# POWER.net
KiCad netlist of a schematic drawn in Altium Designer
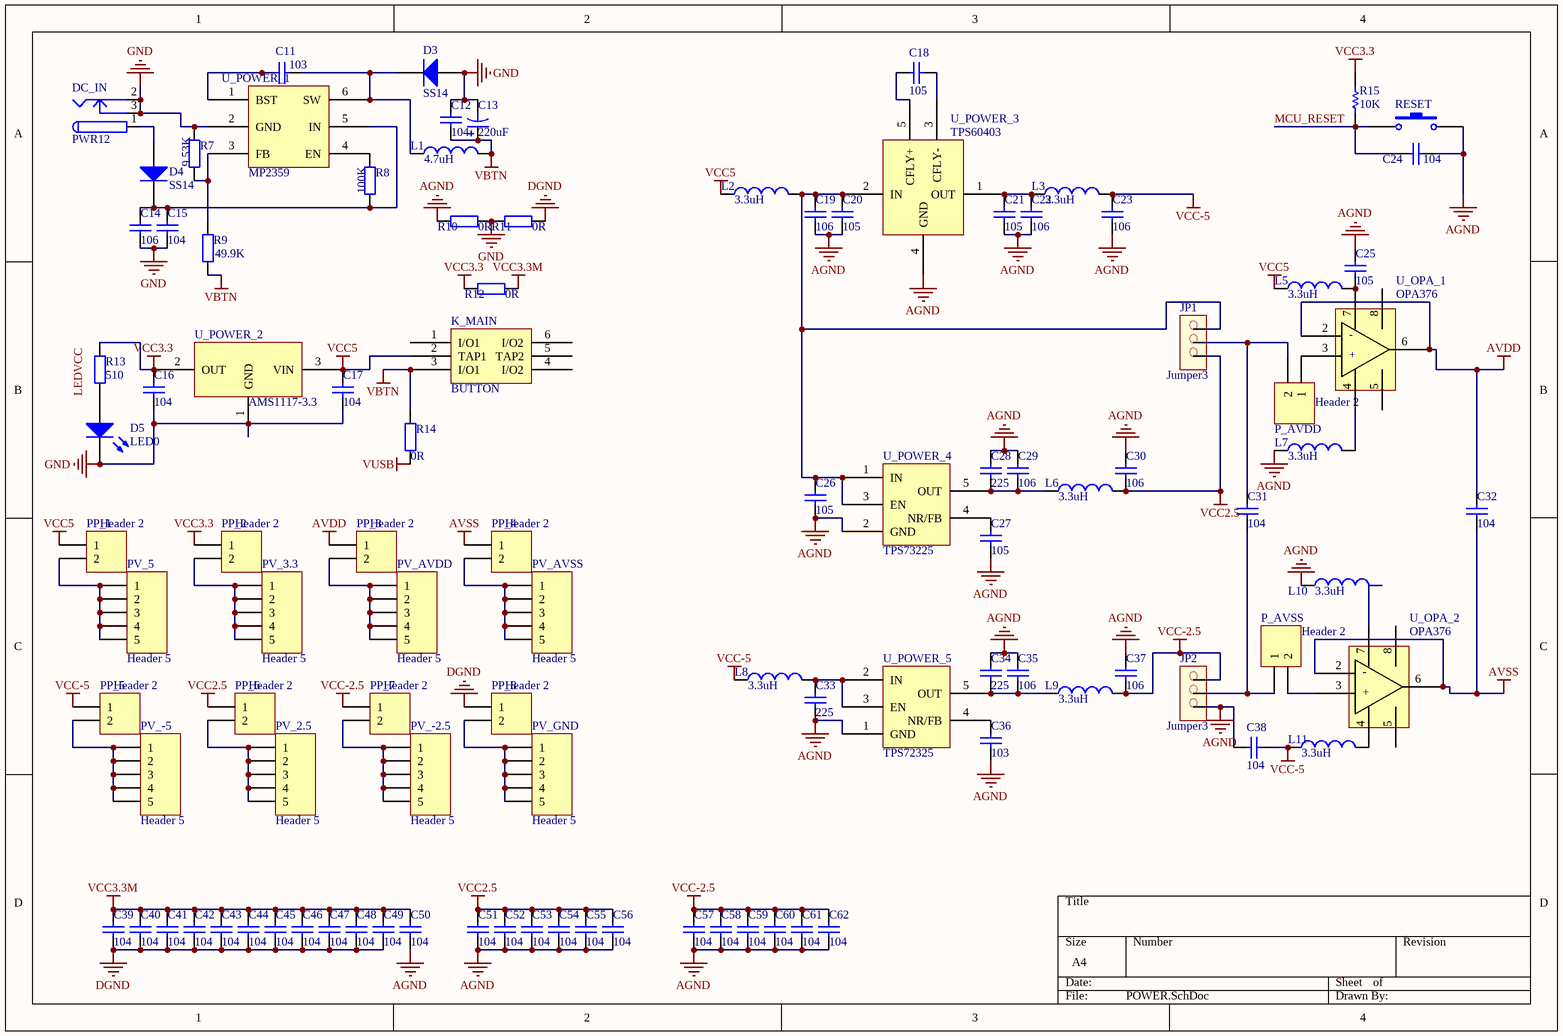
[diagram p0: POWER.SchDoc]

(export (version "E")
  (design (tool "Eeschema 10.0.6"))
  (components
    (comp (ref "C11")
      (value "103")
      (footprint "SMT-0603")
      (description "Capacitor")
      (fields (field (name "Comment") "Cap") (field (name "PUBLISHER") "Altium Limited"))
      (libsource (lib "Miscellaneous Devices") (part "Cap"))
    )
    (comp (ref "C12")
      (value "104")
      (footprint "SMT-0603")
      (description "Capacitor")
      (fields (field (name "Comment") "Cap") (field (name "PUBLISHER") "Altium Limited"))
      (libsource (lib "Miscellaneous Devices") (part "Cap"))
    )
    (comp (ref "C13")
      (value "220uF")
      (footprint "SMT-Cap100~220uF(5x5.4)_10V")
      (description "Polarized Capacitor (Radial)")
      (fields (field (name "Comment") "Cap Pol1") (field (name "PUBLISHER") "Altium Limited"))
      (libsource (lib "Miscellaneous Devices") (part "Cap Pol1"))
    )
    (comp (ref "C14")
      (value "106")
      (footprint "SMT-0603")
      (description "Capacitor")
      (fields (field (name "Comment") "Cap") (field (name "PUBLISHER") "Altium Limited"))
      (libsource (lib "Miscellaneous Devices") (part "Cap"))
    )
    (comp (ref "C15")
      (value "104")
      (footprint "SMT-0603")
      (description "Capacitor")
      (fields (field (name "Comment") "Cap") (field (name "PUBLISHER") "Altium Limited"))
      (libsource (lib "Miscellaneous Devices") (part "Cap"))
    )
    (comp (ref "C16")
      (value "104")
      (footprint "SMT-0603")
      (description "Capacitor")
      (fields (field (name "Comment") "Cap") (field (name "PUBLISHER") "Altium Limited"))
      (libsource (lib "Miscellaneous Devices") (part "Cap"))
    )
    (comp (ref "C17")
      (value "104")
      (footprint "SMT-0603")
      (description "Capacitor")
      (fields (field (name "Comment") "Cap") (field (name "PUBLISHER") "Altium Limited"))
      (libsource (lib "Miscellaneous Devices") (part "Cap"))
    )
    (comp (ref "C18")
      (value "105")
      (footprint "SMT-0603")
      (description "Capacitor")
      (fields (field (name "Comment") "Cap") (field (name "PUBLISHER") "Altium Limited"))
      (libsource (lib "Miscellaneous Devices") (part "Cap"))
    )
    (comp (ref "C19")
      (value "106")
      (footprint "SMT-0603")
      (description "Capacitor")
      (fields (field (name "Comment") "Cap") (field (name "PUBLISHER") "Altium Limited"))
      (libsource (lib "Miscellaneous Devices") (part "Cap"))
    )
    (comp (ref "C20")
      (value "105")
      (footprint "SMT-0603")
      (description "Capacitor")
      (fields (field (name "Comment") "Cap") (field (name "PUBLISHER") "Altium Limited"))
      (libsource (lib "Miscellaneous Devices") (part "Cap"))
    )
    (comp (ref "C21")
      (value "105")
      (footprint "SMT-0603")
      (description "Capacitor")
      (fields (field (name "Comment") "Cap") (field (name "PUBLISHER") "Altium Limited"))
      (libsource (lib "Miscellaneous Devices") (part "Cap"))
    )
    (comp (ref "C22")
      (value "106")
      (footprint "SMT-0603")
      (description "Capacitor")
      (fields (field (name "Comment") "Cap") (field (name "PUBLISHER") "Altium Limited"))
      (libsource (lib "Miscellaneous Devices") (part "Cap"))
    )
    (comp (ref "C23")
      (value "106")
      (footprint "SMT-0603")
      (description "Capacitor")
      (fields (field (name "Comment") "Cap") (field (name "PUBLISHER") "Altium Limited"))
      (libsource (lib "Miscellaneous Devices") (part "Cap"))
    )
    (comp (ref "C24")
      (value "104")
      (footprint "SMT-0603")
      (description "Capacitor")
      (fields (field (name "Comment") "Cap") (field (name "PUBLISHER") "Altium Limited"))
      (libsource (lib "Miscellaneous Devices") (part "Cap"))
    )
    (comp (ref "C25")
      (value "105")
      (footprint "SMT-0603")
      (description "Capacitor")
      (fields (field (name "Comment") "Cap") (field (name "PUBLISHER") "Altium Limited"))
      (libsource (lib "Miscellaneous Devices") (part "Cap"))
    )
    (comp (ref "C26")
      (value "105")
      (footprint "SMT-0603")
      (description "Capacitor")
      (fields (field (name "Comment") "Cap") (field (name "PUBLISHER") "Altium Limited"))
      (libsource (lib "Miscellaneous Devices") (part "Cap"))
    )
    (comp (ref "C27")
      (value "105")
      (footprint "SMT-0603")
      (description "Capacitor")
      (fields (field (name "Comment") "Cap") (field (name "PUBLISHER") "Altium Limited"))
      (libsource (lib "Miscellaneous Devices") (part "Cap"))
    )
    (comp (ref "C28")
      (value "225")
      (footprint "SMT-0603")
      (description "Capacitor")
      (fields (field (name "Comment") "Cap") (field (name "PUBLISHER") "Altium Limited"))
      (libsource (lib "Miscellaneous Devices") (part "Cap"))
    )
    (comp (ref "C29")
      (value "106")
      (footprint "SMT-0603")
      (description "Capacitor")
      (fields (field (name "Comment") "Cap") (field (name "PUBLISHER") "Altium Limited"))
      (libsource (lib "Miscellaneous Devices") (part "Cap"))
    )
    (comp (ref "C30")
      (value "106")
      (footprint "SMT-0603")
      (description "Capacitor")
      (fields (field (name "Comment") "Cap") (field (name "PUBLISHER") "Altium Limited"))
      (libsource (lib "Miscellaneous Devices") (part "Cap"))
    )
    (comp (ref "C31")
      (value "104")
      (footprint "SMT-0603")
      (description "Capacitor")
      (fields (field (name "Comment") "Cap") (field (name "PUBLISHER") "Altium Limited"))
      (libsource (lib "Miscellaneous Devices") (part "Cap"))
    )
    (comp (ref "C32")
      (value "104")
      (footprint "SMT-0603")
      (description "Capacitor")
      (fields (field (name "Comment") "Cap") (field (name "PUBLISHER") "Altium Limited"))
      (libsource (lib "Miscellaneous Devices") (part "Cap"))
    )
    (comp (ref "C33")
      (value "225")
      (footprint "SMT-0603")
      (description "Capacitor")
      (fields (field (name "Comment") "Cap") (field (name "PUBLISHER") "Altium Limited"))
      (libsource (lib "Miscellaneous Devices") (part "Cap"))
    )
    (comp (ref "C34")
      (value "225")
      (footprint "SMT-0603")
      (description "Capacitor")
      (fields (field (name "Comment") "Cap") (field (name "PUBLISHER") "Altium Limited"))
      (libsource (lib "Miscellaneous Devices") (part "Cap"))
    )
    (comp (ref "C35")
      (value "106")
      (footprint "SMT-0603")
      (description "Capacitor")
      (fields (field (name "Comment") "Cap") (field (name "PUBLISHER") "Altium Limited"))
      (libsource (lib "Miscellaneous Devices") (part "Cap"))
    )
    (comp (ref "C36")
      (value "103")
      (footprint "SMT-0603")
      (description "Capacitor")
      (fields (field (name "Comment") "Cap") (field (name "PUBLISHER") "Altium Limited"))
      (libsource (lib "Miscellaneous Devices") (part "Cap"))
    )
    (comp (ref "C37")
      (value "106")
      (footprint "SMT-0603")
      (description "Capacitor")
      (fields (field (name "Comment") "Cap") (field (name "PUBLISHER") "Altium Limited"))
      (libsource (lib "Miscellaneous Devices") (part "Cap"))
    )
    (comp (ref "C38")
      (value "104")
      (footprint "SMT-0603")
      (description "Capacitor")
      (fields (field (name "Comment") "Cap") (field (name "PUBLISHER") "Altium Limited"))
      (libsource (lib "Miscellaneous Devices") (part "Cap"))
    )
    (comp (ref "C39")
      (value "104")
      (footprint "SMT-0603")
      (description "Capacitor")
      (fields (field (name "Comment") "Cap") (field (name "PUBLISHER") "Altium Limited"))
      (libsource (lib "Miscellaneous Devices") (part "Cap"))
    )
    (comp (ref "C40")
      (value "104")
      (footprint "SMT-0603")
      (description "Capacitor")
      (fields (field (name "Comment") "Cap") (field (name "PUBLISHER") "Altium Limited"))
      (libsource (lib "Miscellaneous Devices") (part "Cap"))
    )
    (comp (ref "C41")
      (value "104")
      (footprint "SMT-0603")
      (description "Capacitor")
      (fields (field (name "Comment") "Cap") (field (name "PUBLISHER") "Altium Limited"))
      (libsource (lib "Miscellaneous Devices") (part "Cap"))
    )
    (comp (ref "C42")
      (value "104")
      (footprint "SMT-0603")
      (description "Capacitor")
      (fields (field (name "Comment") "Cap") (field (name "PUBLISHER") "Altium Limited"))
      (libsource (lib "Miscellaneous Devices") (part "Cap"))
    )
    (comp (ref "C43")
      (value "104")
      (footprint "SMT-0603")
      (description "Capacitor")
      (fields (field (name "Comment") "Cap") (field (name "PUBLISHER") "Altium Limited"))
      (libsource (lib "Miscellaneous Devices") (part "Cap"))
    )
    (comp (ref "C44")
      (value "104")
      (footprint "SMT-0603")
      (description "Capacitor")
      (fields (field (name "Comment") "Cap") (field (name "PUBLISHER") "Altium Limited"))
      (libsource (lib "Miscellaneous Devices") (part "Cap"))
    )
    (comp (ref "C45")
      (value "104")
      (footprint "SMT-0603")
      (description "Capacitor")
      (fields (field (name "Comment") "Cap") (field (name "PUBLISHER") "Altium Limited"))
      (libsource (lib "Miscellaneous Devices") (part "Cap"))
    )
    (comp (ref "C46")
      (value "104")
      (footprint "SMT-0603")
      (description "Capacitor")
      (fields (field (name "Comment") "Cap") (field (name "PUBLISHER") "Altium Limited"))
      (libsource (lib "Miscellaneous Devices") (part "Cap"))
    )
    (comp (ref "C47")
      (value "104")
      (footprint "SMT-0603")
      (description "Capacitor")
      (fields (field (name "Comment") "Cap") (field (name "PUBLISHER") "Altium Limited"))
      (libsource (lib "Miscellaneous Devices") (part "Cap"))
    )
    (comp (ref "C48")
      (value "104")
      (footprint "SMT-0603")
      (description "Capacitor")
      (fields (field (name "Comment") "Cap") (field (name "PUBLISHER") "Altium Limited"))
      (libsource (lib "Miscellaneous Devices") (part "Cap"))
    )
    (comp (ref "C49")
      (value "104")
      (footprint "SMT-0603")
      (description "Capacitor")
      (fields (field (name "Comment") "Cap") (field (name "PUBLISHER") "Altium Limited"))
      (libsource (lib "Miscellaneous Devices") (part "Cap"))
    )
    (comp (ref "C50")
      (value "104")
      (footprint "SMT-0603")
      (description "Capacitor")
      (fields (field (name "Comment") "Cap") (field (name "PUBLISHER") "Altium Limited"))
      (libsource (lib "Miscellaneous Devices") (part "Cap"))
    )
    (comp (ref "C51")
      (value "104")
      (footprint "SMT-0603")
      (description "Capacitor")
      (fields (field (name "Comment") "Cap") (field (name "PUBLISHER") "Altium Limited"))
      (libsource (lib "Miscellaneous Devices") (part "Cap"))
    )
    (comp (ref "C52")
      (value "104")
      (footprint "SMT-0603")
      (description "Capacitor")
      (fields (field (name "Comment") "Cap") (field (name "PUBLISHER") "Altium Limited"))
      (libsource (lib "Miscellaneous Devices") (part "Cap"))
    )
    (comp (ref "C53")
      (value "104")
      (footprint "SMT-0603")
      (description "Capacitor")
      (fields (field (name "Comment") "Cap") (field (name "PUBLISHER") "Altium Limited"))
      (libsource (lib "Miscellaneous Devices") (part "Cap"))
    )
    (comp (ref "C54")
      (value "104")
      (footprint "SMT-0603")
      (description "Capacitor")
      (fields (field (name "Comment") "Cap") (field (name "PUBLISHER") "Altium Limited"))
      (libsource (lib "Miscellaneous Devices") (part "Cap"))
    )
    (comp (ref "C55")
      (value "104")
      (footprint "SMT-0603")
      (description "Capacitor")
      (fields (field (name "Comment") "Cap") (field (name "PUBLISHER") "Altium Limited"))
      (libsource (lib "Miscellaneous Devices") (part "Cap"))
    )
    (comp (ref "C56")
      (value "104")
      (footprint "SMT-0603")
      (description "Capacitor")
      (fields (field (name "Comment") "Cap") (field (name "PUBLISHER") "Altium Limited"))
      (libsource (lib "Miscellaneous Devices") (part "Cap"))
    )
    (comp (ref "C57")
      (value "104")
      (footprint "SMT-0603")
      (description "Capacitor")
      (fields (field (name "Comment") "Cap") (field (name "PUBLISHER") "Altium Limited"))
      (libsource (lib "Miscellaneous Devices") (part "Cap"))
    )
    (comp (ref "C58")
      (value "104")
      (footprint "SMT-0603")
      (description "Capacitor")
      (fields (field (name "Comment") "Cap") (field (name "PUBLISHER") "Altium Limited"))
      (libsource (lib "Miscellaneous Devices") (part "Cap"))
    )
    (comp (ref "C59")
      (value "104")
      (footprint "SMT-0603")
      (description "Capacitor")
      (fields (field (name "Comment") "Cap") (field (name "PUBLISHER") "Altium Limited"))
      (libsource (lib "Miscellaneous Devices") (part "Cap"))
    )
    (comp (ref "C60")
      (value "104")
      (footprint "SMT-0603")
      (description "Capacitor")
      (fields (field (name "Comment") "Cap") (field (name "PUBLISHER") "Altium Limited"))
      (libsource (lib "Miscellaneous Devices") (part "Cap"))
    )
    (comp (ref "C61")
      (value "104")
      (footprint "SMT-0603")
      (description "Capacitor")
      (fields (field (name "Comment") "Cap") (field (name "PUBLISHER") "Altium Limited"))
      (libsource (lib "Miscellaneous Devices") (part "Cap"))
    )
    (comp (ref "C62")
      (value "104")
      (footprint "SMT-0603")
      (description "Capacitor")
      (fields (field (name "Comment") "Cap") (field (name "PUBLISHER") "Altium Limited"))
      (libsource (lib "Miscellaneous Devices") (part "Cap"))
    )
    (comp (ref "D3")
      (value "SS14")
      (footprint "SMA")
      (description "3 Amp General Purpose Rectifier")
      (fields (field (name "PUBLISHER") "Altium Limited"))
      (libsource (lib "Miscellaneous Devices") (part "Diode 1N5400"))
    )
    (comp (ref "D4")
      (value "SS14")
      (footprint "SMA")
      (description "3 Amp General Purpose Rectifier")
      (fields (field (name "PUBLISHER") "Altium Limited"))
      (libsource (lib "Miscellaneous Devices") (part "Diode 1N5400"))
    )
    (comp (ref "D5")
      (value "LED0")
      (footprint "K3528")
      (description "Typical INFRARED GaAs LED")
      (fields (field (name "PUBLISHER") "Altium Limited"))
      (libsource (lib "Miscellaneous Devices") (part "LED0"))
    )
    (comp (ref "DC_IN")
      (value "PWR12")
      (footprint "D-DCJACK")
      (description "Low Voltage Power Supply Connector")
      (fields (field (name "PUBLISHER") "Altium Limited"))
      (libsource (lib "Miscellaneous Connectors") (part "PWR2.5"))
    )
    (comp (ref "JP1") (value "Jumper3") (footprint "HDR1X3") (libsource (lib "*") (part "Jumper3")))
    (comp (ref "JP2") (value "Jumper3") (footprint "HDR1X3") (libsource (lib "*") (part "Jumper3")))
    (comp (ref "K_MAIN")
      (value "BUTTON")
      (footprint "Auto_lock_SW_7X7")
      (libsource (lib "STM_ALL") (part "BUTTON"))
    )
    (comp (ref "L1")
      (value "4.7uH")
      (footprint "SMT-0805")
      (description "Inductor")
      (fields (field (name "PUBLISHER") "Altium Limited"))
      (libsource (lib "Miscellaneous Devices") (part "Inductor"))
    )
    (comp (ref "L2")
      (value "3.3uH")
      (footprint "SMT-0805")
      (description "Inductor")
      (fields (field (name "PUBLISHER") "Altium Limited"))
      (libsource (lib "Miscellaneous Devices") (part "Inductor"))
    )
    (comp (ref "L3")
      (value "3.3uH")
      (footprint "SMT-0805")
      (description "Inductor")
      (fields (field (name "PUBLISHER") "Altium Limited"))
      (libsource (lib "Miscellaneous Devices") (part "Inductor"))
    )
    (comp (ref "L5")
      (value "3.3uH")
      (footprint "SMT-0805")
      (description "Inductor")
      (fields (field (name "PUBLISHER") "Altium Limited"))
      (libsource (lib "Miscellaneous Devices") (part "Inductor"))
    )
    (comp (ref "L6")
      (value "3.3uH")
      (footprint "SMT-0805")
      (description "Inductor")
      (fields (field (name "PUBLISHER") "Altium Limited"))
      (libsource (lib "Miscellaneous Devices") (part "Inductor"))
    )
    (comp (ref "L7")
      (value "3.3uH")
      (footprint "SMT-0805")
      (description "Inductor")
      (fields (field (name "PUBLISHER") "Altium Limited"))
      (libsource (lib "Miscellaneous Devices") (part "Inductor"))
    )
    (comp (ref "L8")
      (value "3.3uH")
      (footprint "SMT-0805")
      (description "Inductor")
      (fields (field (name "PUBLISHER") "Altium Limited"))
      (libsource (lib "Miscellaneous Devices") (part "Inductor"))
    )
    (comp (ref "L9")
      (value "3.3uH")
      (footprint "SMT-0805")
      (description "Inductor")
      (fields (field (name "PUBLISHER") "Altium Limited"))
      (libsource (lib "Miscellaneous Devices") (part "Inductor"))
    )
    (comp (ref "L10")
      (value "3.3uH")
      (footprint "SMT-0805")
      (description "Inductor")
      (fields (field (name "PUBLISHER") "Altium Limited"))
      (libsource (lib "Miscellaneous Devices") (part "Inductor"))
    )
    (comp (ref "L11")
      (value "3.3uH")
      (footprint "SMT-0805")
      (description "Inductor")
      (fields (field (name "PUBLISHER") "Altium Limited"))
      (libsource (lib "Miscellaneous Devices") (part "Inductor"))
    )
    (comp (ref "PP_1")
      (value "Header 2")
      (footprint "HDR1X2")
      (description "Header, 2-Pin")
      (fields (field (name "PUBLISHER") "Altium Limited"))
      (libsource (lib "Miscellaneous Connectors") (part "Header 2"))
    )
    (comp (ref "PP_2")
      (value "Header 2")
      (footprint "HDR1X2")
      (description "Header, 2-Pin")
      (fields (field (name "PUBLISHER") "Altium Limited"))
      (libsource (lib "Miscellaneous Connectors") (part "Header 2"))
    )
    (comp (ref "PP_3")
      (value "Header 2")
      (footprint "HDR1X2")
      (description "Header, 2-Pin")
      (fields (field (name "PUBLISHER") "Altium Limited"))
      (libsource (lib "Miscellaneous Connectors") (part "Header 2"))
    )
    (comp (ref "PP_4")
      (value "Header 2")
      (footprint "HDR1X2")
      (description "Header, 2-Pin")
      (fields (field (name "PUBLISHER") "Altium Limited"))
      (libsource (lib "Miscellaneous Connectors") (part "Header 2"))
    )
    (comp (ref "PP_5")
      (value "Header 2")
      (footprint "HDR1X2")
      (description "Header, 2-Pin")
      (fields (field (name "PUBLISHER") "Altium Limited"))
      (libsource (lib "Miscellaneous Connectors") (part "Header 2"))
    )
    (comp (ref "PP_6")
      (value "Header 2")
      (footprint "HDR1X2")
      (description "Header, 2-Pin")
      (fields (field (name "PUBLISHER") "Altium Limited"))
      (libsource (lib "Miscellaneous Connectors") (part "Header 2"))
    )
    (comp (ref "PP_7")
      (value "Header 2")
      (footprint "HDR1X2")
      (description "Header, 2-Pin")
      (fields (field (name "PUBLISHER") "Altium Limited"))
      (libsource (lib "Miscellaneous Connectors") (part "Header 2"))
    )
    (comp (ref "PP_8")
      (value "Header 2")
      (footprint "HDR1X2")
      (description "Header, 2-Pin")
      (fields (field (name "PUBLISHER") "Altium Limited"))
      (libsource (lib "Miscellaneous Connectors") (part "Header 2"))
    )
    (comp (ref "PV_-2.5")
      (value "Header 5")
      (footprint "HDR1X5")
      (description "Header, 5-Pin")
      (fields (field (name "PUBLISHER") "Altium Limited"))
      (libsource (lib "Miscellaneous Connectors") (part "Header 5"))
    )
    (comp (ref "PV_-5")
      (value "Header 5")
      (footprint "HDR1X5")
      (description "Header, 5-Pin")
      (fields (field (name "PUBLISHER") "Altium Limited"))
      (libsource (lib "Miscellaneous Connectors") (part "Header 5"))
    )
    (comp (ref "PV_2.5")
      (value "Header 5")
      (footprint "HDR1X5")
      (description "Header, 5-Pin")
      (fields (field (name "PUBLISHER") "Altium Limited"))
      (libsource (lib "Miscellaneous Connectors") (part "Header 5"))
    )
    (comp (ref "PV_3.3")
      (value "Header 5")
      (footprint "HDR1X5")
      (description "Header, 5-Pin")
      (fields (field (name "PUBLISHER") "Altium Limited"))
      (libsource (lib "Miscellaneous Connectors") (part "Header 5"))
    )
    (comp (ref "PV_5")
      (value "Header 5")
      (footprint "HDR1X5")
      (description "Header, 5-Pin")
      (fields (field (name "PUBLISHER") "Altium Limited"))
      (libsource (lib "Miscellaneous Connectors") (part "Header 5"))
    )
    (comp (ref "PV_AVDD")
      (value "Header 5")
      (footprint "HDR1X5")
      (description "Header, 5-Pin")
      (fields (field (name "PUBLISHER") "Altium Limited"))
      (libsource (lib "Miscellaneous Connectors") (part "Header 5"))
    )
    (comp (ref "PV_AVSS")
      (value "Header 5")
      (footprint "HDR1X5")
      (description "Header, 5-Pin")
      (fields (field (name "PUBLISHER") "Altium Limited"))
      (libsource (lib "Miscellaneous Connectors") (part "Header 5"))
    )
    (comp (ref "PV_GND")
      (value "Header 5")
      (footprint "HDR1X5")
      (description "Header, 5-Pin")
      (fields (field (name "PUBLISHER") "Altium Limited"))
      (libsource (lib "Miscellaneous Connectors") (part "Header 5"))
    )
    (comp (ref "P_AVDD")
      (value "Header 2")
      (footprint "HDR1X2")
      (description "Header, 2-Pin")
      (fields (field (name "PUBLISHER") "Altium Limited"))
      (libsource (lib "") (part "Header 2_1"))
    )
    (comp (ref "P_AVSS")
      (value "Header 2")
      (footprint "HDR1X2")
      (description "Header, 2-Pin")
      (fields (field (name "PUBLISHER") "Altium Limited"))
      (libsource (lib "") (part "Header 2_2"))
    )
    (comp (ref "R7")
      (value "9.53K")
      (footprint "SMT-0603")
      (description "Resistor")
      (fields (field (name "PUBLISHER") "Altium Limited"))
      (libsource (lib "Miscellaneous Devices") (part "Res2"))
    )
    (comp (ref "R8")
      (value "100K")
      (footprint "SMT-0603")
      (description "Resistor")
      (fields (field (name "Comment") "9.53K") (field (name "PUBLISHER") "Altium Limited"))
      (libsource (lib "Miscellaneous Devices") (part "Res2"))
    )
    (comp (ref "R9")
      (value "49.9K")
      (footprint "SMT-0603")
      (description "Resistor")
      (fields (field (name "Comment") "Res2") (field (name "PUBLISHER") "Altium Limited"))
      (libsource (lib "Miscellaneous Devices") (part "Res2"))
    )
    (comp (ref "R10")
      (value "0R")
      (footprint "SMT-0603")
      (description "Resistor")
      (fields (field (name "PUBLISHER") "Altium Limited"))
      (libsource (lib "") (part "Res2_1"))
    )
    (comp (ref "R11")
      (value "0R")
      (footprint "SMT-0603")
      (description "Resistor")
      (fields (field (name "PUBLISHER") "Altium Limited"))
      (libsource (lib "") (part "Res2_1"))
    )
    (comp (ref "R12")
      (value "0R")
      (footprint "SMT-0603")
      (description "Resistor")
      (fields (field (name "PUBLISHER") "Altium Limited"))
      (libsource (lib "") (part "Res2_1"))
    )
    (comp (ref "R13")
      (value "510")
      (footprint "SMT-0603")
      (description "Resistor")
      (fields (field (name "Comment") "Res2") (field (name "PUBLISHER") "Altium Limited"))
      (libsource (lib "Miscellaneous Devices") (part "Res2"))
    )
    (comp (ref "R14")
      (value "0R")
      (footprint "SMT-0603")
      (description "Resistor")
      (fields (field (name "PUBLISHER") "Altium Limited"))
      (libsource (lib "Miscellaneous Devices") (part "Res2"))
    )
    (comp (ref "R15")
      (value "10K")
      (footprint "SMT-0603")
      (description "Resistor")
      (fields (field (name "Comment") "Res1") (field (name "PUBLISHER") "Altium Limited"))
      (libsource (lib "Miscellaneous Devices") (part "Res1"))
    )
    (comp (ref "RESET")
      (value "W-PB")
      (footprint "SW-DEMO_1")
      (description "Switch")
      (fields (field (name "PUBLISHER") "Altium Limited"))
      (libsource (lib "Miscellaneous Devices") (part "SW-PB"))
    )
    (comp (ref "U_OPA_1") (value "OPA376") (footprint "SOP8") (libsource (lib "*") (part "OPA376")))
    (comp (ref "U_OPA_2") (value "OPA376") (footprint "SOP8") (libsource (lib "*") (part "OPA376")))
    (comp (ref "U_POWER_1")
      (value "MP2359")
      (footprint "SOT-23-6")
      (libsource (lib "STM_ALL") (part "MP2359"))
    )
    (comp (ref "U_POWER_2")
      (value "AMS1117-3.3")
      (footprint "SOT223")
      (libsource (lib "STM_ALL") (part "AMS1117"))
    )
    (comp (ref "U_POWER_3") (value "TPS60403") (libsource (lib "STM_ALL") (part "TPS60403")))
    (comp (ref "U_POWER_4") (value "TPS73225") (libsource (lib "STM_ALL") (part "TPS73225")))
    (comp (ref "U_POWER_5") (value "TPS72325") (libsource (lib "STM_ALL") (part "TPS72325")))
  )
  (nets
    (net (code "2") (name "/MCU_RESET") (class "Default")
      (node (ref "C24") (pin "1") (pinfunction "1_1") (pintype "passive"))
      (node (ref "R15") (pin "1") (pinfunction "1_1") (pintype "passive"))
      (node (ref "RESET") (pin "1") (pinfunction "1_1") (pintype "passive"))
    )
    (net (code "3") (name "AGND") (class "Default")
      (node (ref "C19") (pin "1") (pinfunction "1_1") (pintype "passive"))
      (node (ref "C20") (pin "1") (pinfunction "1_1") (pintype "passive"))
      (node (ref "C21") (pin "1") (pinfunction "1_1") (pintype "passive"))
      (node (ref "C22") (pin "1") (pinfunction "1_1") (pintype "passive"))
      (node (ref "C23") (pin "1") (pinfunction "1_1") (pintype "passive"))
      (node (ref "C24") (pin "2") (pinfunction "2_2") (pintype "passive"))
      (node (ref "C25") (pin "2") (pinfunction "2_2") (pintype "passive"))
      (node (ref "C26") (pin "1") (pinfunction "1_1") (pintype "passive"))
      (node (ref "C27") (pin "1") (pinfunction "1_1") (pintype "passive"))
      (node (ref "C28") (pin "2") (pinfunction "2_2") (pintype "passive"))
      (node (ref "C29") (pin "2") (pinfunction "2_2") (pintype "passive"))
      (node (ref "C30") (pin "2") (pinfunction "2_2") (pintype "passive"))
      (node (ref "C33") (pin "1") (pinfunction "1_1") (pintype "passive"))
      (node (ref "C34") (pin "2") (pinfunction "2_2") (pintype "passive"))
      (node (ref "C35") (pin "2") (pinfunction "2_2") (pintype "passive"))
      (node (ref "C36") (pin "1") (pinfunction "1_1") (pintype "passive"))
      (node (ref "C37") (pin "2") (pinfunction "2_2") (pintype "passive"))
      (node (ref "C38") (pin "1") (pinfunction "1_1") (pintype "passive"))
      (node (ref "C50") (pin "1") (pinfunction "1_1") (pintype "passive"))
      (node (ref "C51") (pin "1") (pinfunction "1_1") (pintype "passive"))
      (node (ref "C52") (pin "1") (pinfunction "1_1") (pintype "passive"))
      (node (ref "C53") (pin "1") (pinfunction "1_1") (pintype "passive"))
      (node (ref "C54") (pin "1") (pinfunction "1_1") (pintype "passive"))
      (node (ref "C55") (pin "1") (pinfunction "1_1") (pintype "passive"))
      (node (ref "C56") (pin "1") (pinfunction "1_1") (pintype "passive"))
      (node (ref "C57") (pin "1") (pinfunction "1_1") (pintype "passive"))
      (node (ref "C58") (pin "1") (pinfunction "1_1") (pintype "passive"))
      (node (ref "C59") (pin "1") (pinfunction "1_1") (pintype "passive"))
      (node (ref "C60") (pin "1") (pinfunction "1_1") (pintype "passive"))
      (node (ref "C61") (pin "1") (pinfunction "1_1") (pintype "passive"))
      (node (ref "C62") (pin "1") (pinfunction "1_1") (pintype "passive"))
      (node (ref "JP2") (pin "1") (pinfunction "0_1") (pintype "passive"))
      (node (ref "L10") (pin "1") (pinfunction "1_1") (pintype "passive"))
      (node (ref "L7") (pin "1") (pinfunction "1_1") (pintype "passive"))
      (node (ref "R10") (pin "1") (pinfunction "1_1") (pintype "passive"))
      (node (ref "RESET") (pin "2") (pinfunction "2_2") (pintype "passive"))
      (node (ref "U_POWER_3") (pin "4") (pinfunction "GND_4") (pintype "passive"))
      (node (ref "U_POWER_4") (pin "2") (pinfunction "GND_2") (pintype "passive"))
      (node (ref "U_POWER_5") (pin "1") (pinfunction "GND_1") (pintype "passive"))
    )
    (net (code "4") (name "AVDD") (class "Default")
      (node (ref "C32") (pin "2") (pinfunction "2_2") (pintype "passive"))
      (node (ref "PP_3") (pin "1") (pinfunction "1_1") (pintype "passive"))
      (node (ref "U_OPA_1") (pin "2") (pintype "passive"))
      (node (ref "U_OPA_1") (pin "6") (pintype "passive"))
    )
    (net (code "5") (name "AVSS") (class "Default")
      (node (ref "C32") (pin "1") (pinfunction "1_1") (pintype "passive"))
      (node (ref "PP_4") (pin "1") (pinfunction "1_1") (pintype "passive"))
      (node (ref "U_OPA_2") (pin "2") (pintype "passive"))
      (node (ref "U_OPA_2") (pin "6") (pintype "passive"))
    )
    (net (code "6") (name "DGND") (class "Default")
      (node (ref "C39") (pin "1") (pinfunction "1_1") (pintype "passive"))
      (node (ref "C40") (pin "1") (pinfunction "1_1") (pintype "passive"))
      (node (ref "C41") (pin "1") (pinfunction "1_1") (pintype "passive"))
      (node (ref "C42") (pin "1") (pinfunction "1_1") (pintype "passive"))
      (node (ref "C43") (pin "1") (pinfunction "1_1") (pintype "passive"))
      (node (ref "C44") (pin "1") (pinfunction "1_1") (pintype "passive"))
      (node (ref "C45") (pin "1") (pinfunction "1_1") (pintype "passive"))
      (node (ref "C46") (pin "1") (pinfunction "1_1") (pintype "passive"))
      (node (ref "C47") (pin "1") (pinfunction "1_1") (pintype "passive"))
      (node (ref "C48") (pin "1") (pinfunction "1_1") (pintype "passive"))
      (node (ref "C49") (pin "1") (pinfunction "1_1") (pintype "passive"))
      (node (ref "PP_8") (pin "1") (pinfunction "1_1") (pintype "passive"))
      (node (ref "R11") (pin "2") (pinfunction "2_2") (pintype "passive"))
    )
    (net (code "7") (name "GND") (class "Default")
      (node (ref "C12") (pin "2") (pinfunction "2_2") (pintype "passive"))
      (node (ref "C13") (pin "2") (pinfunction "2_2") (pintype "passive"))
      (node (ref "C14") (pin "2") (pinfunction "2_2") (pintype "passive"))
      (node (ref "C15") (pin "2") (pinfunction "2_2") (pintype "passive"))
      (node (ref "C16") (pin "1") (pinfunction "1_1") (pintype "passive"))
      (node (ref "C17") (pin "1") (pinfunction "1_1") (pintype "passive"))
      (node (ref "D3") (pin "1") (pinfunction "A_1") (pintype "passive"))
      (node (ref "D5") (pin "2") (pinfunction "K_2") (pintype "passive"))
      (node (ref "DC_IN") (pin "2") (pinfunction "2_2") (pintype "power_in"))
      (node (ref "DC_IN") (pin "3") (pinfunction "3_3") (pintype "power_in"))
      (node (ref "R10") (pin "2") (pinfunction "2_2") (pintype "passive"))
      (node (ref "R11") (pin "1") (pinfunction "1_1") (pintype "passive"))
      (node (ref "R7") (pin "2") (pinfunction "2_2") (pintype "passive"))
      (node (ref "U_POWER_1") (pin "2") (pinfunction "GND_2") (pintype "passive"))
      (node (ref "U_POWER_2") (pin "1") (pinfunction "GND_1") (pintype "passive"))
    )
    (net (code "8") (name "Net-(C25-Pad1)") (class "Default")
      (node (ref "C25") (pin "1") (pinfunction "1_1") (pintype "passive"))
      (node (ref "L5") (pin "2") (pinfunction "2_2") (pintype "passive"))
      (node (ref "U_OPA_1") (pin "7") (pintype "passive"))
    )
    (net (code "9") (name "Net-(D3-K)") (class "Default")
      (node (ref "C11") (pin "1") (pinfunction "1_1") (pintype "passive"))
      (node (ref "D3") (pin "2") (pinfunction "K_2") (pintype "passive"))
      (node (ref "L1") (pin "1") (pinfunction "1_1") (pintype "passive"))
      (node (ref "U_POWER_1") (pin "6") (pinfunction "SW_6") (pintype "passive"))
    )
    (net (code "10") (name "Net-(D4-A)") (class "Default")
      (node (ref "D4") (pin "1") (pinfunction "A_1") (pintype "passive"))
      (node (ref "DC_IN") (pin "1") (pinfunction "1_1") (pintype "power_in"))
    )
    (net (code "11") (name "Net-(D4-K)") (class "Default")
      (node (ref "C14") (pin "1") (pinfunction "1_1") (pintype "passive"))
      (node (ref "C15") (pin "1") (pinfunction "1_1") (pintype "passive"))
      (node (ref "D4") (pin "2") (pinfunction "K_2") (pintype "passive"))
      (node (ref "R8") (pin "1") (pinfunction "1_1") (pintype "passive"))
      (node (ref "U_POWER_1") (pin "5") (pinfunction "IN_5") (pintype "passive"))
    )
    (net (code "12") (name "Net-(D5-A)") (class "Default")
      (node (ref "D5") (pin "1") (pinfunction "A_1") (pintype "passive"))
      (node (ref "R13") (pin "1") (pinfunction "1_1") (pintype "passive"))
    )
    (net (code "13") (name "Net-(JP1-1)") (class "Default")
      (node (ref "C31") (pin "2") (pinfunction "2_2") (pintype "passive"))
      (node (ref "JP1") (pin "2") (pinfunction "1_2") (pintype "passive"))
      (node (ref "P_AVDD") (pin "2") (pinfunction "2_2") (pintype "passive"))
    )
    (net (code "14") (name "Net-(JP2-1)") (class "Default")
      (node (ref "C31") (pin "1") (pinfunction "1_1") (pintype "passive"))
      (node (ref "JP2") (pin "2") (pinfunction "1_2") (pintype "passive"))
      (node (ref "P_AVSS") (pin "1") (pinfunction "1_1") (pintype "passive"))
    )
    (net (code "15") (name "Net-(L7-Pad2)") (class "Default")
      (node (ref "L7") (pin "2") (pinfunction "2_2") (pintype "passive"))
      (node (ref "U_OPA_1") (pin "4") (pintype "passive"))
    )
    (net (code "16") (name "Net-(L10-Pad2)") (class "Default")
      (node (ref "L10") (pin "2") (pinfunction "2_2") (pintype "passive"))
      (node (ref "U_OPA_2") (pin "7") (pintype "passive"))
    )
    (net (code "17") (name "Net-(L11-Pad2)") (class "Default")
      (node (ref "L11") (pin "2") (pinfunction "2_2") (pintype "passive"))
      (node (ref "U_OPA_2") (pin "4") (pintype "passive"))
    )
    (net (code "18") (name "Net-(PP_1-Pad2)") (class "Default")
      (node (ref "PP_1") (pin "2") (pinfunction "2_2") (pintype "passive"))
      (node (ref "PV_5") (pin "1") (pinfunction "1_1") (pintype "passive"))
      (node (ref "PV_5") (pin "2") (pinfunction "2_2") (pintype "passive"))
      (node (ref "PV_5") (pin "3") (pinfunction "3_3") (pintype "passive"))
      (node (ref "PV_5") (pin "4") (pinfunction "4_4") (pintype "passive"))
      (node (ref "PV_5") (pin "5") (pinfunction "5_5") (pintype "passive"))
    )
    (net (code "19") (name "Net-(PP_2-Pad2)") (class "Default")
      (node (ref "PP_2") (pin "2") (pinfunction "2_2") (pintype "passive"))
      (node (ref "PV_3.3") (pin "1") (pinfunction "1_1") (pintype "passive"))
      (node (ref "PV_3.3") (pin "2") (pinfunction "2_2") (pintype "passive"))
      (node (ref "PV_3.3") (pin "3") (pinfunction "3_3") (pintype "passive"))
      (node (ref "PV_3.3") (pin "4") (pinfunction "4_4") (pintype "passive"))
      (node (ref "PV_3.3") (pin "5") (pinfunction "5_5") (pintype "passive"))
    )
    (net (code "20") (name "Net-(PP_3-Pad2)") (class "Default")
      (node (ref "PP_3") (pin "2") (pinfunction "2_2") (pintype "passive"))
      (node (ref "PV_AVDD") (pin "1") (pinfunction "1_1") (pintype "passive"))
      (node (ref "PV_AVDD") (pin "2") (pinfunction "2_2") (pintype "passive"))
      (node (ref "PV_AVDD") (pin "3") (pinfunction "3_3") (pintype "passive"))
      (node (ref "PV_AVDD") (pin "4") (pinfunction "4_4") (pintype "passive"))
      (node (ref "PV_AVDD") (pin "5") (pinfunction "5_5") (pintype "passive"))
    )
    (net (code "21") (name "Net-(PP_4-Pad2)") (class "Default")
      (node (ref "PP_4") (pin "2") (pinfunction "2_2") (pintype "passive"))
      (node (ref "PV_AVSS") (pin "1") (pinfunction "1_1") (pintype "passive"))
      (node (ref "PV_AVSS") (pin "2") (pinfunction "2_2") (pintype "passive"))
      (node (ref "PV_AVSS") (pin "3") (pinfunction "3_3") (pintype "passive"))
      (node (ref "PV_AVSS") (pin "4") (pinfunction "4_4") (pintype "passive"))
      (node (ref "PV_AVSS") (pin "5") (pinfunction "5_5") (pintype "passive"))
    )
    (net (code "22") (name "Net-(PP_5-Pad2)") (class "Default")
      (node (ref "PP_5") (pin "2") (pinfunction "2_2") (pintype "passive"))
      (node (ref "PV_-5") (pin "1") (pinfunction "1_1") (pintype "passive"))
      (node (ref "PV_-5") (pin "2") (pinfunction "2_2") (pintype "passive"))
      (node (ref "PV_-5") (pin "3") (pinfunction "3_3") (pintype "passive"))
      (node (ref "PV_-5") (pin "4") (pinfunction "4_4") (pintype "passive"))
      (node (ref "PV_-5") (pin "5") (pinfunction "5_5") (pintype "passive"))
    )
    (net (code "23") (name "Net-(PP_6-Pad2)") (class "Default")
      (node (ref "PP_6") (pin "2") (pinfunction "2_2") (pintype "passive"))
      (node (ref "PV_2.5") (pin "1") (pinfunction "1_1") (pintype "passive"))
      (node (ref "PV_2.5") (pin "2") (pinfunction "2_2") (pintype "passive"))
      (node (ref "PV_2.5") (pin "3") (pinfunction "3_3") (pintype "passive"))
      (node (ref "PV_2.5") (pin "4") (pinfunction "4_4") (pintype "passive"))
      (node (ref "PV_2.5") (pin "5") (pinfunction "5_5") (pintype "passive"))
    )
    (net (code "24") (name "Net-(PP_7-Pad2)") (class "Default")
      (node (ref "PP_7") (pin "2") (pinfunction "2_2") (pintype "passive"))
      (node (ref "PV_-2.5") (pin "1") (pinfunction "1_1") (pintype "passive"))
      (node (ref "PV_-2.5") (pin "2") (pinfunction "2_2") (pintype "passive"))
      (node (ref "PV_-2.5") (pin "3") (pinfunction "3_3") (pintype "passive"))
      (node (ref "PV_-2.5") (pin "4") (pinfunction "4_4") (pintype "passive"))
      (node (ref "PV_-2.5") (pin "5") (pinfunction "5_5") (pintype "passive"))
    )
    (net (code "25") (name "Net-(PP_8-Pad2)") (class "Default")
      (node (ref "PP_8") (pin "2") (pinfunction "2_2") (pintype "passive"))
      (node (ref "PV_GND") (pin "1") (pinfunction "1_1") (pintype "passive"))
      (node (ref "PV_GND") (pin "2") (pinfunction "2_2") (pintype "passive"))
      (node (ref "PV_GND") (pin "3") (pinfunction "3_3") (pintype "passive"))
      (node (ref "PV_GND") (pin "4") (pinfunction "4_4") (pintype "passive"))
      (node (ref "PV_GND") (pin "5") (pinfunction "5_5") (pintype "passive"))
    )
    (net (code "26") (name "Net-(P_AVDD-Pad1)") (class "Default")
      (node (ref "P_AVDD") (pin "1") (pinfunction "1_1") (pintype "passive"))
      (node (ref "U_OPA_1") (pin "3") (pintype "passive"))
    )
    (net (code "27") (name "Net-(P_AVSS-Pad2)") (class "Default")
      (node (ref "P_AVSS") (pin "2") (pinfunction "2_2") (pintype "passive"))
      (node (ref "U_OPA_2") (pin "3") (pintype "passive"))
    )
    (net (code "28") (name "Net-(U_POWER_1-BST)") (class "Default")
      (node (ref "C11") (pin "2") (pinfunction "2_2") (pintype "passive"))
      (node (ref "U_POWER_1") (pin "1") (pinfunction "BST_1") (pintype "passive"))
    )
    (net (code "29") (name "Net-(U_POWER_1-EN)") (class "Default")
      (node (ref "R8") (pin "2") (pinfunction "2_2") (pintype "passive"))
      (node (ref "U_POWER_1") (pin "4") (pinfunction "EN_4") (pintype "passive"))
    )
    (net (code "30") (name "Net-(U_POWER_1-FB)") (class "Default")
      (node (ref "R7") (pin "1") (pinfunction "1_1") (pintype "passive"))
      (node (ref "R9") (pin "2") (pinfunction "2_2") (pintype "passive"))
      (node (ref "U_POWER_1") (pin "3") (pinfunction "FB_3") (pintype "passive"))
    )
    (net (code "31") (name "Net-(U_POWER_3-CFLY+)") (class "Default")
      (node (ref "C18") (pin "1") (pinfunction "1_1") (pintype "passive"))
      (node (ref "U_POWER_3") (pin "5") (pinfunction "CFLY+_5") (pintype "passive"))
    )
    (net (code "32") (name "Net-(U_POWER_3-CFLY-)") (class "Default")
      (node (ref "C18") (pin "2") (pinfunction "2_2") (pintype "passive"))
      (node (ref "U_POWER_3") (pin "3") (pinfunction "CFLY-_3") (pintype "passive"))
    )
    (net (code "33") (name "Net-(U_POWER_3-IN)") (class "Default")
      (node (ref "C19") (pin "2") (pinfunction "2_2") (pintype "passive"))
      (node (ref "C20") (pin "2") (pinfunction "2_2") (pintype "passive"))
      (node (ref "C26") (pin "2") (pinfunction "2_2") (pintype "passive"))
      (node (ref "JP1") (pin "3") (pinfunction "3_3") (pintype "passive"))
      (node (ref "L2") (pin "2") (pinfunction "2_2") (pintype "passive"))
      (node (ref "U_POWER_3") (pin "2") (pinfunction "IN_2") (pintype "passive"))
      (node (ref "U_POWER_4") (pin "1") (pinfunction "IN_1") (pintype "passive"))
      (node (ref "U_POWER_4") (pin "3") (pinfunction "EN_3") (pintype "passive"))
    )
    (net (code "34") (name "Net-(U_POWER_3-OUT)") (class "Default")
      (node (ref "C21") (pin "2") (pinfunction "2_2") (pintype "passive"))
      (node (ref "C22") (pin "2") (pinfunction "2_2") (pintype "passive"))
      (node (ref "L3") (pin "1") (pinfunction "1_1") (pintype "passive"))
      (node (ref "U_POWER_3") (pin "1") (pinfunction "OUT_1") (pintype "passive"))
    )
    (net (code "35") (name "Net-(U_POWER_4-NR{slash}FB)") (class "Default")
      (node (ref "C27") (pin "2") (pinfunction "2_2") (pintype "passive"))
      (node (ref "U_POWER_4") (pin "4") (pinfunction "NR/FB_4") (pintype "passive"))
    )
    (net (code "36") (name "Net-(U_POWER_4-OUT)") (class "Default")
      (node (ref "C28") (pin "1") (pinfunction "1_1") (pintype "passive"))
      (node (ref "C29") (pin "1") (pinfunction "1_1") (pintype "passive"))
      (node (ref "L6") (pin "1") (pinfunction "1_1") (pintype "passive"))
      (node (ref "U_POWER_4") (pin "5") (pinfunction "OUT_5") (pintype "passive"))
    )
    (net (code "37") (name "Net-(U_POWER_5-EN)") (class "Default")
      (node (ref "C33") (pin "2") (pinfunction "2_2") (pintype "passive"))
      (node (ref "L8") (pin "2") (pinfunction "2_2") (pintype "passive"))
      (node (ref "U_POWER_5") (pin "2") (pinfunction "IN_2") (pintype "passive"))
      (node (ref "U_POWER_5") (pin "3") (pinfunction "EN_3") (pintype "passive"))
    )
    (net (code "38") (name "Net-(U_POWER_5-NR{slash}FB)") (class "Default")
      (node (ref "C36") (pin "2") (pinfunction "2_2") (pintype "passive"))
      (node (ref "U_POWER_5") (pin "4") (pinfunction "NR/FB_4") (pintype "passive"))
    )
    (net (code "39") (name "Net-(U_POWER_5-OUT)") (class "Default")
      (node (ref "C34") (pin "1") (pinfunction "1_1") (pintype "passive"))
      (node (ref "C35") (pin "1") (pinfunction "1_1") (pintype "passive"))
      (node (ref "L9") (pin "1") (pinfunction "1_1") (pintype "passive"))
      (node (ref "U_POWER_5") (pin "5") (pinfunction "OUT_5") (pintype "passive"))
    )
    (net (code "40") (name "VBTN") (class "Default")
      (node (ref "C12") (pin "1") (pinfunction "1_1") (pintype "passive"))
      (node (ref "C13") (pin "1") (pinfunction "1_1") (pintype "passive"))
      (node (ref "K_MAIN") (pin "3") (pinfunction "I/O1_3") (pintype "passive"))
      (node (ref "L1") (pin "2") (pinfunction "2_2") (pintype "passive"))
      (node (ref "R14") (pin "2") (pinfunction "2_2") (pintype "passive"))
      (node (ref "R9") (pin "1") (pinfunction "1_1") (pintype "passive"))
    )
    (net (code "41") (name "VCC-2.5") (class "Default")
      (node (ref "C37") (pin "1") (pinfunction "1_1") (pintype "passive"))
      (node (ref "C57") (pin "2") (pinfunction "2_2") (pintype "passive"))
      (node (ref "C58") (pin "2") (pinfunction "2_2") (pintype "passive"))
      (node (ref "C59") (pin "2") (pinfunction "2_2") (pintype "passive"))
      (node (ref "C60") (pin "2") (pinfunction "2_2") (pintype "passive"))
      (node (ref "C61") (pin "2") (pinfunction "2_2") (pintype "passive"))
      (node (ref "C62") (pin "2") (pinfunction "2_2") (pintype "passive"))
      (node (ref "JP2") (pin "3") (pinfunction "3_3") (pintype "passive"))
      (node (ref "L9") (pin "2") (pinfunction "2_2") (pintype "passive"))
      (node (ref "PP_7") (pin "1") (pinfunction "1_1") (pintype "passive"))
    )
    (net (code "42") (name "VCC-5") (class "Default")
      (node (ref "C23") (pin "2") (pinfunction "2_2") (pintype "passive"))
      (node (ref "C38") (pin "2") (pinfunction "2_2") (pintype "passive"))
      (node (ref "L11") (pin "1") (pinfunction "1_1") (pintype "passive"))
      (node (ref "L3") (pin "2") (pinfunction "2_2") (pintype "passive"))
      (node (ref "L8") (pin "1") (pinfunction "1_1") (pintype "passive"))
      (node (ref "PP_5") (pin "1") (pinfunction "1_1") (pintype "passive"))
    )
    (net (code "43") (name "VCC2.5") (class "Default")
      (node (ref "C30") (pin "1") (pinfunction "1_1") (pintype "passive"))
      (node (ref "C51") (pin "2") (pinfunction "2_2") (pintype "passive"))
      (node (ref "C52") (pin "2") (pinfunction "2_2") (pintype "passive"))
      (node (ref "C53") (pin "2") (pinfunction "2_2") (pintype "passive"))
      (node (ref "C54") (pin "2") (pinfunction "2_2") (pintype "passive"))
      (node (ref "C55") (pin "2") (pinfunction "2_2") (pintype "passive"))
      (node (ref "C56") (pin "2") (pinfunction "2_2") (pintype "passive"))
      (node (ref "JP1") (pin "1") (pinfunction "0_1") (pintype "passive"))
      (node (ref "L6") (pin "2") (pinfunction "2_2") (pintype "passive"))
      (node (ref "PP_6") (pin "1") (pinfunction "1_1") (pintype "passive"))
    )
    (net (code "44") (name "VCC3.3") (class "Default")
      (node (ref "C16") (pin "2") (pinfunction "2_2") (pintype "passive"))
      (node (ref "PP_2") (pin "1") (pinfunction "1_1") (pintype "passive"))
      (node (ref "R12") (pin "1") (pinfunction "1_1") (pintype "passive"))
      (node (ref "R13") (pin "2") (pinfunction "2_2") (pintype "passive"))
      (node (ref "R15") (pin "2") (pinfunction "2_2") (pintype "passive"))
      (node (ref "U_POWER_2") (pin "2") (pinfunction "OUT_2") (pintype "passive"))
    )
    (net (code "45") (name "VCC3.3M") (class "Default")
      (node (ref "C39") (pin "2") (pinfunction "2_2") (pintype "passive"))
      (node (ref "C40") (pin "2") (pinfunction "2_2") (pintype "passive"))
      (node (ref "C41") (pin "2") (pinfunction "2_2") (pintype "passive"))
      (node (ref "C42") (pin "2") (pinfunction "2_2") (pintype "passive"))
      (node (ref "C43") (pin "2") (pinfunction "2_2") (pintype "passive"))
      (node (ref "C44") (pin "2") (pinfunction "2_2") (pintype "passive"))
      (node (ref "C45") (pin "2") (pinfunction "2_2") (pintype "passive"))
      (node (ref "C46") (pin "2") (pinfunction "2_2") (pintype "passive"))
      (node (ref "C47") (pin "2") (pinfunction "2_2") (pintype "passive"))
      (node (ref "C48") (pin "2") (pinfunction "2_2") (pintype "passive"))
      (node (ref "C49") (pin "2") (pinfunction "2_2") (pintype "passive"))
      (node (ref "C50") (pin "2") (pinfunction "2_2") (pintype "passive"))
      (node (ref "R12") (pin "2") (pinfunction "2_2") (pintype "passive"))
    )
    (net (code "46") (name "VCC5") (class "Default")
      (node (ref "C17") (pin "2") (pinfunction "2_2") (pintype "passive"))
      (node (ref "K_MAIN") (pin "2") (pinfunction "TAP1_2") (pintype "passive"))
      (node (ref "L2") (pin "1") (pinfunction "1_1") (pintype "passive"))
      (node (ref "L5") (pin "1") (pinfunction "1_1") (pintype "passive"))
      (node (ref "PP_1") (pin "1") (pinfunction "1_1") (pintype "passive"))
      (node (ref "U_POWER_2") (pin "3") (pinfunction "VIN_3") (pintype "passive"))
    )
    (net (code "47") (name "VUSB") (class "Default")
      (node (ref "R14") (pin "1") (pinfunction "1_1") (pintype "passive"))
    )
    (net (code "48") (name "unconnected-(K_MAIN-I{slash}O1-Pad1)") (class "Default")
      (node (ref "K_MAIN") (pin "1") (pinfunction "I/O1_1") (pintype "passive"))
    )
    (net (code "49") (name "unconnected-(K_MAIN-I{slash}O2-Pad4)") (class "Default")
      (node (ref "K_MAIN") (pin "4") (pinfunction "I/O2_4") (pintype "passive"))
    )
    (net (code "50") (name "unconnected-(K_MAIN-I{slash}O2-Pad6)") (class "Default")
      (node (ref "K_MAIN") (pin "6") (pinfunction "I/O2_6") (pintype "passive"))
    )
    (net (code "51") (name "unconnected-(K_MAIN-TAP2-Pad5)") (class "Default")
      (node (ref "K_MAIN") (pin "5") (pinfunction "TAP2_5") (pintype "passive"))
    )
    (net (code "52") (name "unconnected-(U_OPA_1-Pad5)") (class "Default")
      (node (ref "U_OPA_1") (pin "5") (pintype "passive"))
    )
    (net (code "53") (name "unconnected-(U_OPA_1-Pad8)") (class "Default")
      (node (ref "U_OPA_1") (pin "8") (pintype "passive"))
    )
    (net (code "54") (name "unconnected-(U_OPA_2-Pad5)") (class "Default")
      (node (ref "U_OPA_2") (pin "5") (pintype "passive"))
    )
    (net (code "55") (name "unconnected-(U_OPA_2-Pad8)") (class "Default")
      (node (ref "U_OPA_2") (pin "8") (pintype "passive"))
    )
  )
)
